# Microcontroleur.net
KiCad netlist of a schematic drawn in Altium Designer
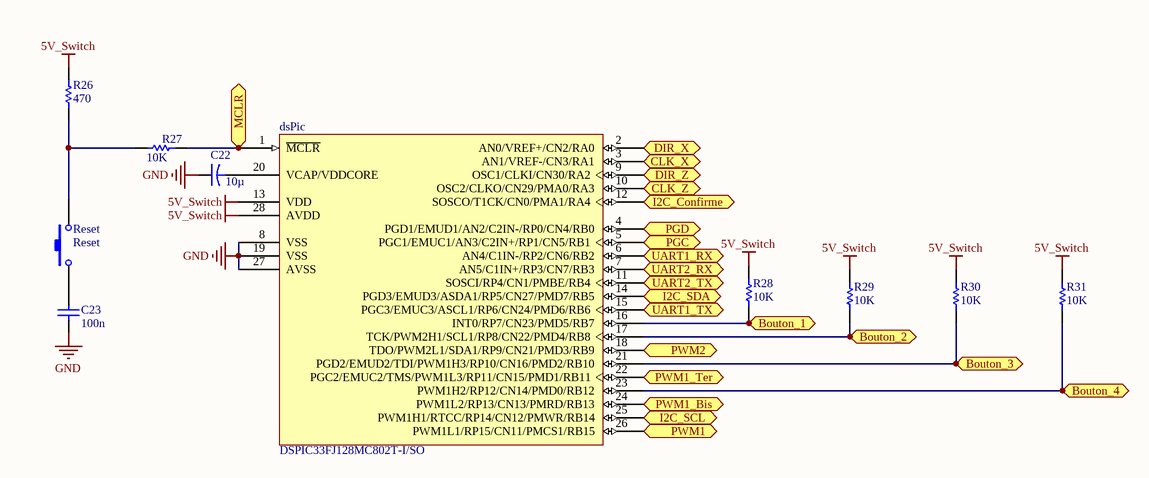
[diagram p0: Microcontroleur.SchDoc]

(export (version "E")
  (design (tool "Eeschema 10.0.6"))
  (components
    (comp (ref "C22")
      (value "10µ")
      (footprint "CAPR5-4X5")
      (fields (field (name "Comment") "Cap2") (field (name "PUBLISHER") "Altium Limited"))
      (libsource (lib "Miscellaneous Devices") (part "Cap2"))
    )
    (comp (ref "C23")
      (value "100n")
      (footprint "0805")
      (fields (field (name "Comment") "Cap") (field (name "PUBLISHER") "Altium Limited"))
      (libsource (lib "Miscellaneous Devices") (part "Cap"))
    )
    (comp (ref "dsPic")
      (value "DSPIC33FJ128MC802T-I/SO")
      (footprint "SOIC-SO28_N")
      (fields (field (name "PUBLISHER") "Altium Limited"))
      (libsource (lib "Microchip DSC 16-Bit dsPIC33F") (part "DSPIC33FJ128MC802T-I/SO"))
    )
    (comp (ref "R26")
      (value "470")
      (footprint "0805")
      (description "470R")
      (fields (field (name "Comment") "Res1") (field (name "PUBLISHER") "Altium Limited"))
      (libsource (lib "Miscellaneous Devices") (part "Res*"))
    )
    (comp (ref "R27")
      (value "10K")
      (footprint "0805")
      (description "10k")
      (fields (field (name "Comment") "Res1") (field (name "PUBLISHER") "Altium Limited"))
      (libsource (lib "Miscellaneous Devices") (part "Res*"))
    )
    (comp (ref "R28")
      (value "10K")
      (footprint "0805")
      (description "10k")
      (fields (field (name "Comment") "Res1") (field (name "PUBLISHER") "Altium Limited"))
      (libsource (lib "Miscellaneous Devices") (part "Res*"))
    )
    (comp (ref "R29")
      (value "10K")
      (footprint "0805")
      (description "10k")
      (fields (field (name "Comment") "Res1") (field (name "PUBLISHER") "Altium Limited"))
      (libsource (lib "Miscellaneous Devices") (part "Res*"))
    )
    (comp (ref "R30")
      (value "10K")
      (footprint "0805")
      (description "10k")
      (fields (field (name "Comment") "Res1") (field (name "PUBLISHER") "Altium Limited"))
      (libsource (lib "Miscellaneous Devices") (part "Res*"))
    )
    (comp (ref "R31")
      (value "10K")
      (footprint "0805")
      (description "10k")
      (fields (field (name "Comment") "Res1") (field (name "PUBLISHER") "Altium Limited"))
      (libsource (lib "Miscellaneous Devices") (part "Res*"))
    )
    (comp (ref "Reset")
      (value "Reset")
      (footprint "SPST-2")
      (description "Bouton Reset")
      (fields (field (name "PUBLISHER") "Altium Limited"))
      (libsource (lib "Miscellaneous Devices") (part "SW-PB"))
    )
  )
  (nets
    (net (code "1") (name "/Bouton_1") (class "Default")
      (node (ref "R28") (pin "2") (pinfunction "2_2") (pintype "passive"))
      (node (ref "dsPic") (pin "16") (pinfunction "INT0/RP7/CN23/PMD5/RB7_16") (pintype "bidirectional"))
    )
    (net (code "2") (name "/Bouton_2") (class "Default")
      (node (ref "R29") (pin "2") (pinfunction "2_2") (pintype "passive"))
      (node (ref "dsPic") (pin "17") (pinfunction "TCK/PWM2H1/SCL1/RP8/CN22/PMD4/RB8_17") (pintype "bidirectional"))
    )
    (net (code "3") (name "/Bouton_3") (class "Default")
      (node (ref "R30") (pin "2") (pinfunction "2_2") (pintype "passive"))
      (node (ref "dsPic") (pin "21") (pinfunction "PGD2/EMUD2/TDI/PWM1H3/RP10/CN16/PMD2/RB10_21") (pintype "bidirectional"))
    )
    (net (code "4") (name "/Bouton_4") (class "Default")
      (node (ref "R31") (pin "2") (pinfunction "2_2") (pintype "passive"))
      (node (ref "dsPic") (pin "23") (pinfunction "PWM1H2/RP12/CN14/PMD0/RB12_23") (pintype "bidirectional"))
    )
    (net (code "5") (name "/CLK_X") (class "Default")
      (node (ref "dsPic") (pin "3") (pinfunction "AN1/VREF-/CN3/RA1_3") (pintype "bidirectional"))
    )
    (net (code "6") (name "/CLK_Z") (class "Default")
      (node (ref "dsPic") (pin "10") (pinfunction "OSC2/CLKO/CN29/PMA0/RA3_10") (pintype "bidirectional"))
    )
    (net (code "7") (name "/DIR_X") (class "Default")
      (node (ref "dsPic") (pin "2") (pinfunction "AN0/VREF+/CN2/RA0_2") (pintype "bidirectional"))
    )
    (net (code "8") (name "/DIR_Z") (class "Default")
      (node (ref "dsPic") (pin "9") (pinfunction "OSC1/CLKI/CN30/RA2_9") (pintype "bidirectional"))
    )
    (net (code "9") (name "/I2C_Confirme") (class "Default")
      (node (ref "dsPic") (pin "12") (pinfunction "SOSCO/T1CK/CN0/PMA1/RA4_12") (pintype "bidirectional"))
    )
    (net (code "10") (name "/I2C_SCL") (class "Default")
      (node (ref "dsPic") (pin "25") (pinfunction "PWM1H1/RTCC/RP14/CN12/PMWR/RB14_25") (pintype "bidirectional"))
    )
    (net (code "11") (name "/I2C_SDA") (class "Default")
      (node (ref "dsPic") (pin "14") (pinfunction "PGD3/EMUD3/ASDA1/RP5/CN27/PMD7/RB5_14") (pintype "bidirectional"))
    )
    (net (code "12") (name "/MCLR") (class "Default")
      (node (ref "R27") (pin "2") (pinfunction "2_2") (pintype "passive"))
      (node (ref "dsPic") (pin "1") (pinfunction "~{MCLR}_1") (pintype "input"))
    )
    (net (code "13") (name "/PGC") (class "Default")
      (node (ref "dsPic") (pin "5") (pinfunction "PGC1/EMUC1/AN3/C2IN+/RP1/CN5/RB1_5") (pintype "bidirectional"))
    )
    (net (code "14") (name "/PGD") (class "Default")
      (node (ref "dsPic") (pin "4") (pinfunction "PGD1/EMUD1/AN2/C2IN-/RP0/CN4/RB0_4") (pintype "bidirectional"))
    )
    (net (code "15") (name "/PWM1") (class "Default")
      (node (ref "dsPic") (pin "26") (pinfunction "PWM1L1/RP15/CN11/PMCS1/RB15_26") (pintype "bidirectional"))
    )
    (net (code "16") (name "/PWM1_Bis") (class "Default")
      (node (ref "dsPic") (pin "24") (pinfunction "PWM1L2/RP13/CN13/PMRD/RB13_24") (pintype "bidirectional"))
    )
    (net (code "17") (name "/PWM1_Ter") (class "Default")
      (node (ref "dsPic") (pin "22") (pinfunction "PGC2/EMUC2/TMS/PWM1L3/RP11/CN15/PMD1/RB11_22") (pintype "bidirectional"))
    )
    (net (code "18") (name "/PWM2") (class "Default")
      (node (ref "dsPic") (pin "18") (pinfunction "TDO/PWM2L1/SDA1/RP9/CN21/PMD3/RB9_18") (pintype "bidirectional"))
    )
    (net (code "19") (name "/UART1_RX") (class "Default")
      (node (ref "dsPic") (pin "6") (pinfunction "AN4/C1IN-/RP2/CN6/RB2_6") (pintype "bidirectional"))
    )
    (net (code "20") (name "/UART1_TX") (class "Default")
      (node (ref "dsPic") (pin "15") (pinfunction "PGC3/EMUC3/ASCL1/RP6/CN24/PMD6/RB6_15") (pintype "bidirectional"))
    )
    (net (code "21") (name "/UART2_RX") (class "Default")
      (node (ref "dsPic") (pin "7") (pinfunction "AN5/C1IN+/RP3/CN7/RB3_7") (pintype "bidirectional"))
    )
    (net (code "22") (name "/UART2_TX") (class "Default")
      (node (ref "dsPic") (pin "11") (pinfunction "SOSCI/RP4/CN1/PMBE/RB4_11") (pintype "bidirectional"))
    )
    (net (code "23") (name "5V_Switch") (class "Default")
      (node (ref "R26") (pin "2") (pinfunction "2_2") (pintype "passive"))
      (node (ref "R28") (pin "1") (pinfunction "1_1") (pintype "passive"))
      (node (ref "R29") (pin "1") (pinfunction "1_1") (pintype "passive"))
      (node (ref "R30") (pin "1") (pinfunction "1_1") (pintype "passive"))
      (node (ref "R31") (pin "1") (pinfunction "1_1") (pintype "passive"))
      (node (ref "dsPic") (pin "13") (pinfunction "VDD_13") (pintype "power_in"))
      (node (ref "dsPic") (pin "28") (pinfunction "AVDD_28") (pintype "power_in"))
    )
    (net (code "24") (name "GND") (class "Default")
      (node (ref "C22") (pin "1") (pinfunction "1_1") (pintype "passive"))
      (node (ref "C23") (pin "2") (pinfunction "2_2") (pintype "passive"))
      (node (ref "dsPic") (pin "19") (pinfunction "VSS_19") (pintype "power_in"))
      (node (ref "dsPic") (pin "27") (pinfunction "AVSS_27") (pintype "power_in"))
      (node (ref "dsPic") (pin "8") (pinfunction "VSS_8") (pintype "power_in"))
    )
    (net (code "25") (name "Net-(C23-Pad1)") (class "Default")
      (node (ref "C23") (pin "1") (pinfunction "1_1") (pintype "passive"))
      (node (ref "Reset") (pin "1") (pinfunction "1_1") (pintype "passive"))
    )
    (net (code "26") (name "Net-(R26-Pad1)") (class "Default")
      (node (ref "R26") (pin "1") (pinfunction "1_1") (pintype "passive"))
      (node (ref "R27") (pin "1") (pinfunction "1_1") (pintype "passive"))
      (node (ref "Reset") (pin "2") (pinfunction "2_2") (pintype "passive"))
    )
    (net (code "27") (name "Net-(dsPic-VCAP{slash}VDDCORE)") (class "Default")
      (node (ref "C22") (pin "2") (pinfunction "2_2") (pintype "passive"))
      (node (ref "dsPic") (pin "20") (pinfunction "VCAP/VDDCORE_20") (pintype "power_in"))
    )
  )
)
